# acceleration_particul_ariel.net
KiCad netlist of a schematic drawn in EasyEDA
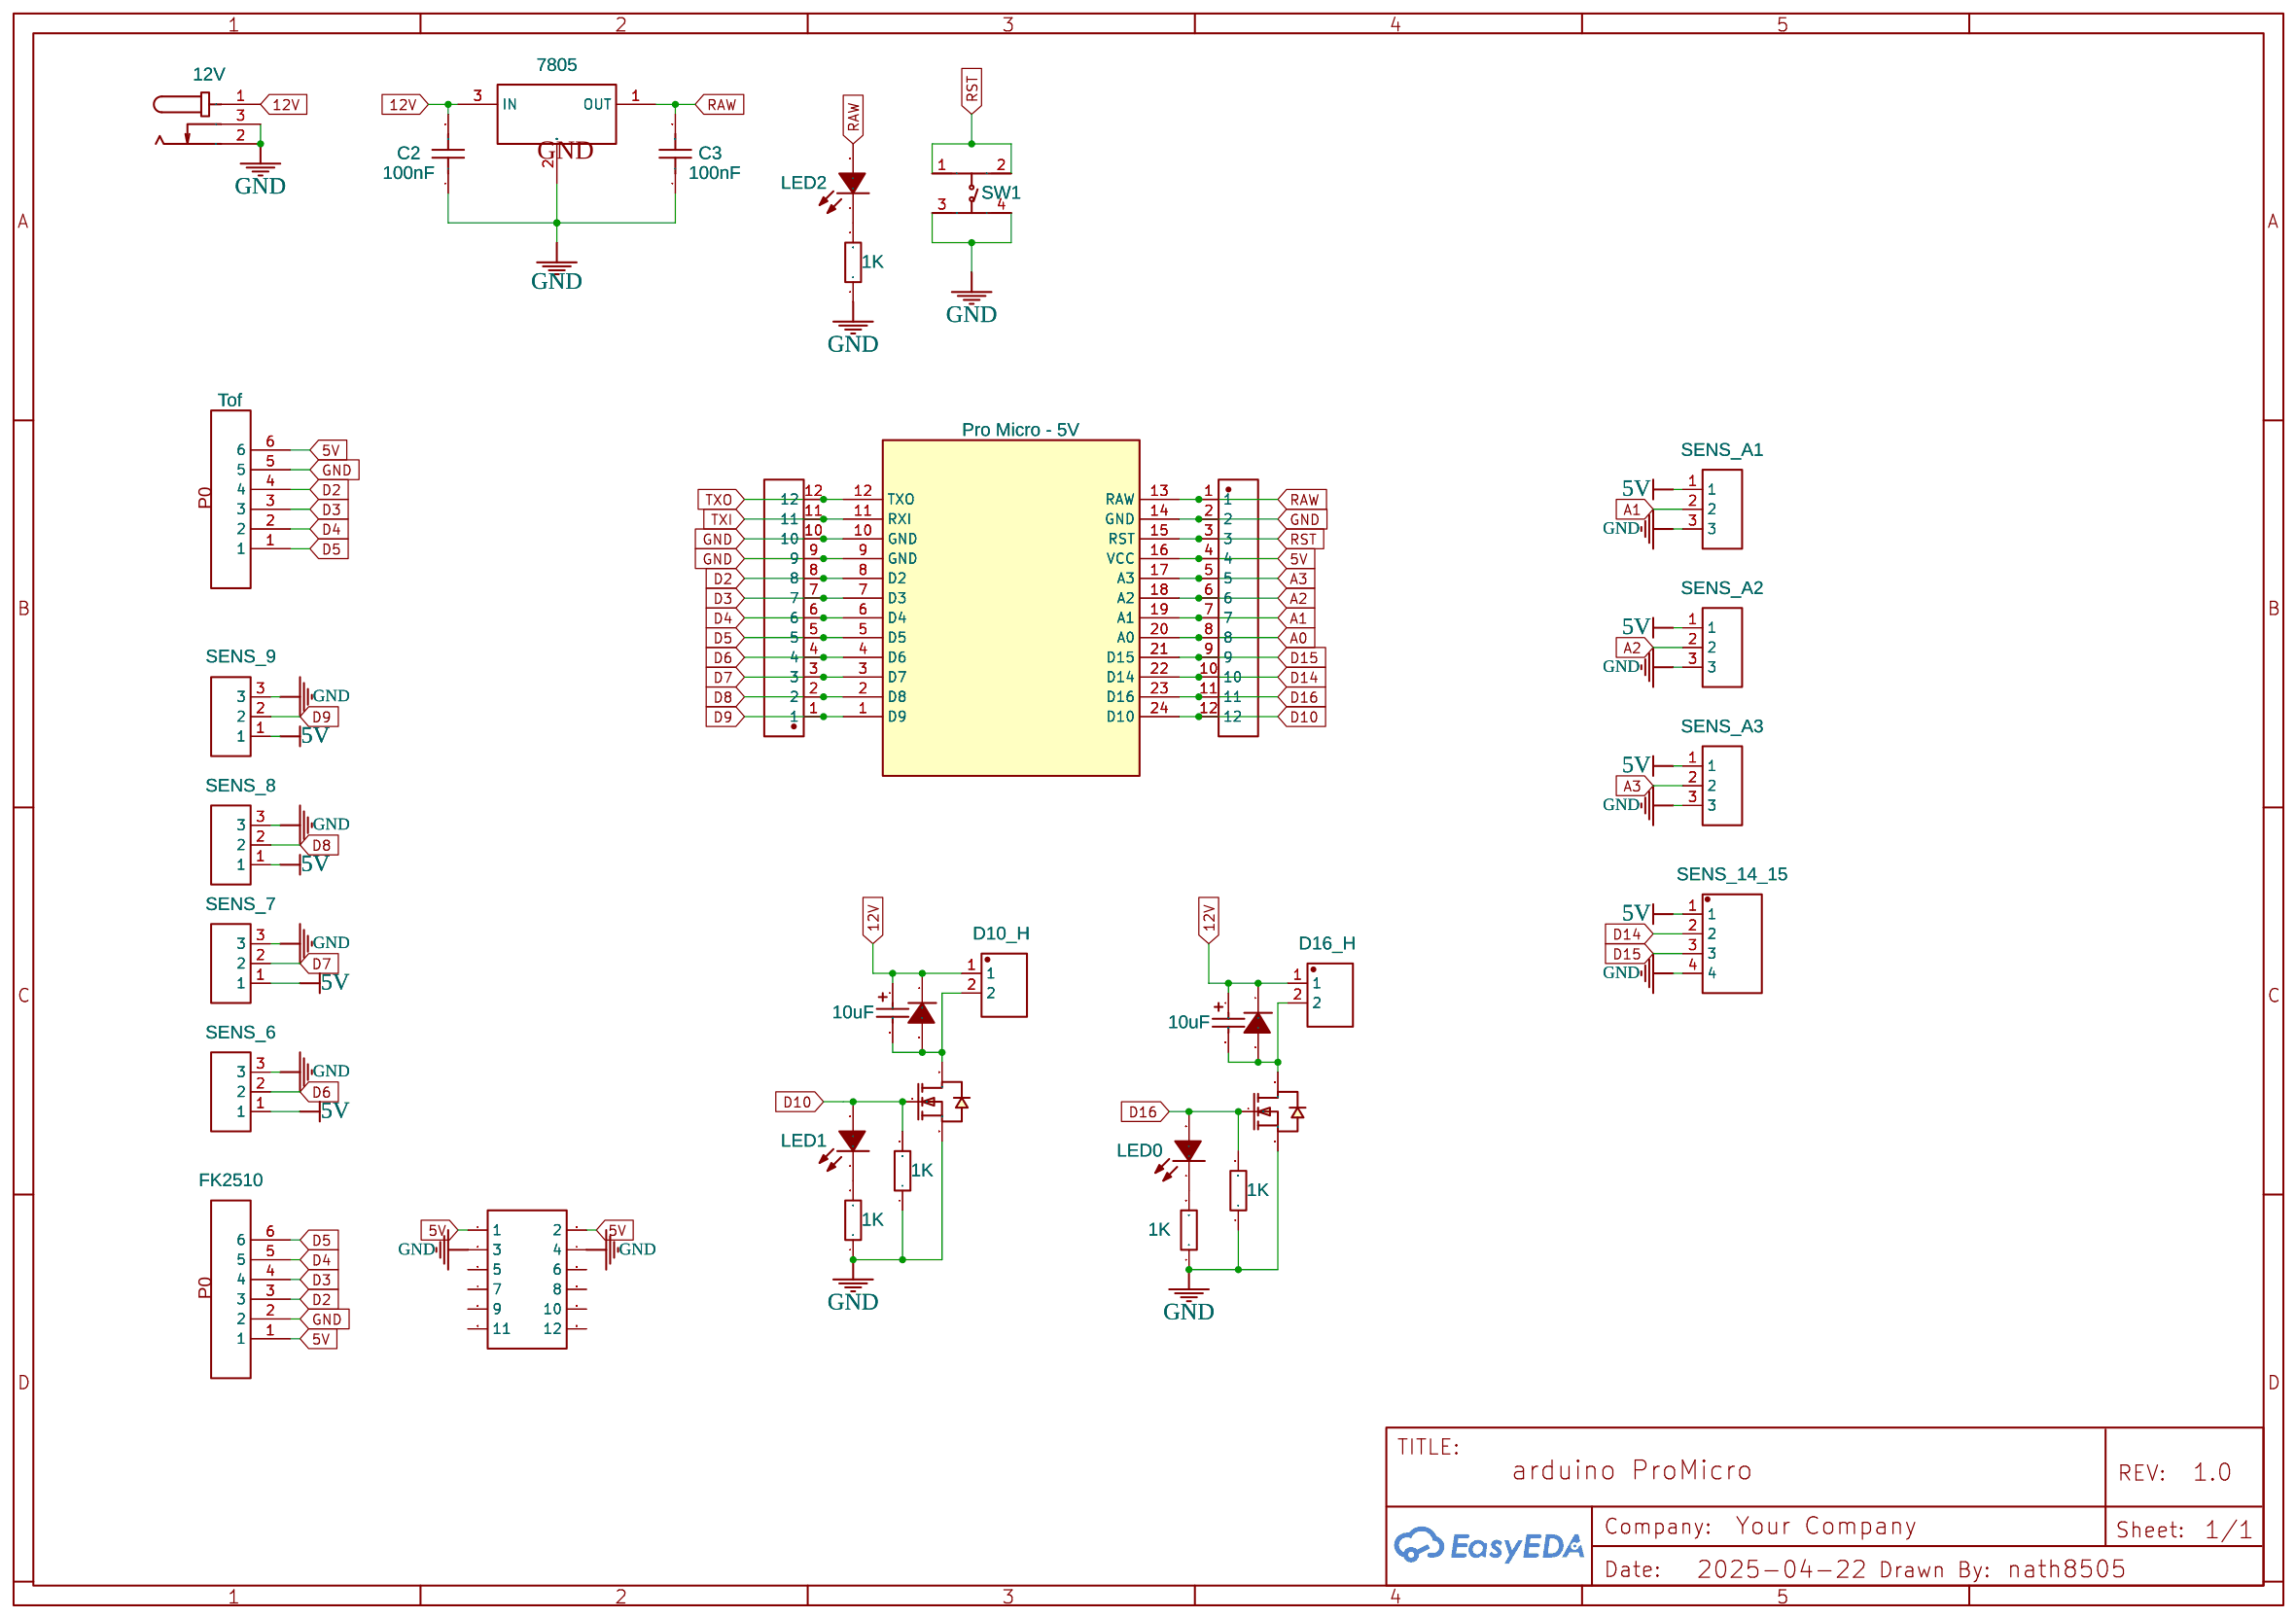
[diagram p0: schematic sheet]

(export (version "E")
  (design (tool "Eeschema 10.0.6"))
  (components
    (comp (ref "12V")
      (value "12V")
      (fields (field (name "Manufacturer Part") "DC005-2.0MM") (field (name "Manufacturer") "SOFNG"))
      (libsource (lib "") (part "DC005-2.0MM"))
    )
    (comp (ref "7805")
      (value "SE78L05")
      (fields (field (name "Manufacturer") "SEAWARD(思旺)"))
      (libsource (lib "") (part "SE78L05"))
    )
    (comp (ref "C0") (value "10uF") (libsource (lib "") (part "TAJA106K016RNJ")))
    (comp (ref "C1") (value "10uF") (libsource (lib "") (part "TAJA106K016RNJ")))
    (comp (ref "C2") (value "100nF") (libsource (lib "") (part "CC0603KRX7R9BB104")))
    (comp (ref "C3") (value "100nF") (libsource (lib "") (part "CC0603KRX7R9BB104")))
    (comp (ref "D0")
      (value "1N4007")
      (fields (field (name "Manufacturer Part") "1N4007F") (field (name "Manufacturer") "SK"))
      (libsource (lib "") (part "1N4007F"))
    )
    (comp (ref "D1")
      (value "1N4007")
      (fields (field (name "Manufacturer Part") "1N4007F") (field (name "Manufacturer") "SK"))
      (libsource (lib "") (part "1N4007F"))
    )
    (comp (ref "D10_H")
      (value "KF2510-2A")
      (fields (field (name "Manufacturer") "BOOMELE"))
      (libsource (lib "") (part "KF2510-2A_1"))
    )
    (comp (ref "D16_H")
      (value "KF2510-2A")
      (fields (field (name "Manufacturer") "BOOMELE"))
      (libsource (lib "") (part "KF2510-2A"))
    )
    (comp (ref "H1")
      (value "h")
      (fields (field (name "Manufacturer Part") "DS1021-1x12SF11-B") (field (name "Manufacturer") "CONNFLY"))
      (libsource (lib "") (part "DS1021-1X12SF11-B_1"))
    )
    (comp (ref "H2")
      (value "h")
      (fields (field (name "Manufacturer Part") "DS1021-1x12SF11-B") (field (name "Manufacturer") "CONNFLY"))
      (libsource (lib "") (part "DS1021-1X12SF11-B"))
    )
    (comp (ref "H4")
      (value "Header-Female-2.54_2x6")
      (fields (field (name "Manufacturer Part") "2.54-2*6P母") (field (name "Manufacturer") "BOOMELE(博穆精密)"))
      (libsource (lib "") (part "Header-Female-2.54_2x6"))
    )
    (comp (ref "I2C_TOF1") (value "Tof") (libsource (lib "") (part "PinHeader6")))
    (comp (ref "I2C_TOF2") (value "FK2510") (libsource (lib "") (part "PinHeader6")))
    (comp (ref "LED0")
      (value "KT-0603R")
      (fields (field (name "Manufacturer") "KENTO"))
      (libsource (lib "") (part "KT-0603R"))
    )
    (comp (ref "LED1")
      (value "KT-0603R")
      (fields (field (name "Manufacturer") "KENTO"))
      (libsource (lib "") (part "KT-0603R"))
    )
    (comp (ref "LED2")
      (value "KT-0603R")
      (fields (field (name "Manufacturer") "KENTO"))
      (libsource (lib "") (part "KT-0603R"))
    )
    (comp (ref "P2") (value "Pro Micro - 5V") (libsource (lib "") (part "Pro Micro - 5V")))
    (comp (ref "R0")
      (value "1K")
      (fields (field (name "Manufacturer Part") "0603WAF1001T5E") (field (name "Manufacturer") "UniOhm"))
      (libsource (lib "") (part "0603WAF1001T5E"))
    )
    (comp (ref "R1")
      (value "1K")
      (fields (field (name "Manufacturer Part") "0603WAF1001T5E") (field (name "Manufacturer") "UniOhm"))
      (libsource (lib "") (part "0603WAF1001T5E"))
    )
    (comp (ref "R2")
      (value "1K")
      (fields (field (name "Manufacturer Part") "0603WAF1001T5E") (field (name "Manufacturer") "UniOhm"))
      (libsource (lib "") (part "0603WAF1001T5E"))
    )
    (comp (ref "R3")
      (value "1K")
      (fields (field (name "Manufacturer Part") "0603WAF1001T5E") (field (name "Manufacturer") "UniOhm"))
      (libsource (lib "") (part "0603WAF1001T5E"))
    )
    (comp (ref "R4")
      (value "1K")
      (fields (field (name "Manufacturer Part") "0603WAF1001T5E") (field (name "Manufacturer") "UniOhm"))
      (libsource (lib "") (part "0603WAF1001T5E"))
    )
    (comp (ref "SENS_6") (value "FK2510") (libsource (lib "") (part "kf2510_3A")))
    (comp (ref "SENS_7") (value "FK2510") (libsource (lib "") (part "kf2510_3A")))
    (comp (ref "SENS_8") (value "FK2510") (libsource (lib "") (part "kf2510_3A")))
    (comp (ref "SENS_9") (value "FK2510") (libsource (lib "") (part "kf2510_3A")))
    (comp (ref "SENS_14_15")
      (value "SENS_14_15")
      (fields
        (field (name "Manufacturer Part") "210S-1*4P L=11.6MMGold-plated black")
        (field (name "Manufacturer") "Ckmtw")
      )
      (libsource (lib "") (part "Conector KF2510_3A.ventilador.4pin"))
    )
    (comp (ref "SENS_A1") (value "FK2510") (libsource (lib "") (part "kf2510_3A_1")))
    (comp (ref "SENS_A2") (value "FK2510") (libsource (lib "") (part "kf2510_3A_1")))
    (comp (ref "SENS_A3") (value "FK2510") (libsource (lib "") (part "kf2510_3A_1")))
    (comp (ref "SW1")
      (value "TC-6610-7-160G")
      (fields (field (name "Manufacturer") "HCTL(华灿天禄)"))
      (libsource (lib "") (part "TC-6610-7-160G"))
    )
    (comp (ref "T1")
      (value "Q")
      (fields (field (name "Manufacturer Part") "AO3400") (field (name "Manufacturer") "ElecSuper(静芯微）"))
      (libsource (lib "") (part "JSM2302"))
    )
    (comp (ref "T2")
      (value "Q")
      (fields (field (name "Manufacturer Part") "AO3400") (field (name "Manufacturer") "ElecSuper(静芯微）"))
      (libsource (lib "") (part "JSM2302"))
    )
  )
  (nets
    (net (code "1") (name "5V") (class "Default")
      (node (ref "H1") (pin "4") (pinfunction "4_4") (pintype "unspecified"))
      (node (ref "H4") (pin "1") (pinfunction "1_1") (pintype "input"))
      (node (ref "H4") (pin "2") (pinfunction "2_2") (pintype "input"))
      (node (ref "I2C_TOF1") (pin "6") (pinfunction "6_6") (pintype "unspecified"))
      (node (ref "I2C_TOF2") (pin "1") (pinfunction "1_1") (pintype "unspecified"))
      (node (ref "P2") (pin "16") (pinfunction "VCC_16") (pintype "unspecified"))
      (node (ref "SENS_14_15") (pin "1") (pinfunction "1_1") (pintype "unspecified"))
      (node (ref "SENS_6") (pin "1") (pinfunction "1_1") (pintype "unspecified"))
      (node (ref "SENS_7") (pin "1") (pinfunction "1_1") (pintype "unspecified"))
      (node (ref "SENS_8") (pin "1") (pinfunction "1_1") (pintype "unspecified"))
      (node (ref "SENS_9") (pin "1") (pinfunction "1_1") (pintype "unspecified"))
      (node (ref "SENS_A1") (pin "1") (pinfunction "1_1") (pintype "unspecified"))
      (node (ref "SENS_A2") (pin "1") (pinfunction "1_1") (pintype "unspecified"))
      (node (ref "SENS_A3") (pin "1") (pinfunction "1_1") (pintype "unspecified"))
    )
    (net (code "2") (name "12V") (class "Default")
      (node (ref "12V") (pin "1") (pinfunction "1_1") (pintype "unspecified"))
      (node (ref "7805") (pin "3") (pinfunction "IN_3") (pintype "passive"))
      (node (ref "C0") (pin "1") (pinfunction "1_1") (pintype "input"))
      (node (ref "C1") (pin "1") (pinfunction "1_1") (pintype "input"))
      (node (ref "C2") (pin "2") (pinfunction "2_2") (pintype "unspecified"))
      (node (ref "D0") (pin "1") (pinfunction "C_1") (pintype "unspecified"))
      (node (ref "D1") (pin "1") (pinfunction "C_1") (pintype "unspecified"))
      (node (ref "D10_H") (pin "1") (pinfunction "1_1") (pintype "unspecified"))
      (node (ref "D16_H") (pin "1") (pinfunction "1_1") (pintype "unspecified"))
    )
    (net (code "3") (name "A0") (class "Default")
      (node (ref "H1") (pin "8") (pinfunction "8_8") (pintype "unspecified"))
      (node (ref "P2") (pin "20") (pinfunction "A0_20") (pintype "unspecified"))
    )
    (net (code "4") (name "A1") (class "Default")
      (node (ref "H1") (pin "7") (pinfunction "7_7") (pintype "unspecified"))
      (node (ref "P2") (pin "19") (pinfunction "A1_19") (pintype "unspecified"))
      (node (ref "SENS_A1") (pin "2") (pinfunction "2_2") (pintype "unspecified"))
    )
    (net (code "5") (name "A2") (class "Default")
      (node (ref "H1") (pin "6") (pinfunction "6_6") (pintype "unspecified"))
      (node (ref "P2") (pin "18") (pinfunction "A2_18") (pintype "unspecified"))
      (node (ref "SENS_A2") (pin "2") (pinfunction "2_2") (pintype "unspecified"))
    )
    (net (code "6") (name "A3") (class "Default")
      (node (ref "H1") (pin "5") (pinfunction "5_5") (pintype "unspecified"))
      (node (ref "P2") (pin "17") (pinfunction "A3_17") (pintype "unspecified"))
      (node (ref "SENS_A3") (pin "2") (pinfunction "2_2") (pintype "unspecified"))
    )
    (net (code "7") (name "D2") (class "Default")
      (node (ref "H2") (pin "8") (pinfunction "8_8") (pintype "unspecified"))
      (node (ref "I2C_TOF1") (pin "4") (pinfunction "4_4") (pintype "unspecified"))
      (node (ref "I2C_TOF2") (pin "3") (pinfunction "3_3") (pintype "unspecified"))
      (node (ref "P2") (pin "8") (pinfunction "D2_8") (pintype "unspecified"))
    )
    (net (code "8") (name "D3") (class "Default")
      (node (ref "H2") (pin "7") (pinfunction "7_7") (pintype "unspecified"))
      (node (ref "I2C_TOF1") (pin "3") (pinfunction "3_3") (pintype "unspecified"))
      (node (ref "I2C_TOF2") (pin "4") (pinfunction "4_4") (pintype "unspecified"))
      (node (ref "P2") (pin "7") (pinfunction "D3_7") (pintype "unspecified"))
    )
    (net (code "9") (name "D4") (class "Default")
      (node (ref "H2") (pin "6") (pinfunction "6_6") (pintype "unspecified"))
      (node (ref "I2C_TOF1") (pin "2") (pinfunction "2_2") (pintype "unspecified"))
      (node (ref "I2C_TOF2") (pin "5") (pinfunction "5_5") (pintype "unspecified"))
      (node (ref "P2") (pin "6") (pinfunction "D4_6") (pintype "unspecified"))
    )
    (net (code "10") (name "D5") (class "Default")
      (node (ref "H2") (pin "5") (pinfunction "5_5") (pintype "unspecified"))
      (node (ref "I2C_TOF1") (pin "1") (pinfunction "1_1") (pintype "unspecified"))
      (node (ref "I2C_TOF2") (pin "6") (pinfunction "6_6") (pintype "unspecified"))
      (node (ref "P2") (pin "5") (pinfunction "D5_5") (pintype "unspecified"))
    )
    (net (code "11") (name "D6") (class "Default")
      (node (ref "H2") (pin "4") (pinfunction "4_4") (pintype "unspecified"))
      (node (ref "P2") (pin "4") (pinfunction "D6_4") (pintype "unspecified"))
      (node (ref "SENS_6") (pin "2") (pinfunction "2_2") (pintype "unspecified"))
    )
    (net (code "12") (name "D7") (class "Default")
      (node (ref "H2") (pin "3") (pinfunction "3_3") (pintype "unspecified"))
      (node (ref "P2") (pin "3") (pinfunction "D7_3") (pintype "unspecified"))
      (node (ref "SENS_7") (pin "2") (pinfunction "2_2") (pintype "unspecified"))
    )
    (net (code "13") (name "D8") (class "Default")
      (node (ref "H2") (pin "2") (pinfunction "2_2") (pintype "unspecified"))
      (node (ref "P2") (pin "2") (pinfunction "D8_2") (pintype "unspecified"))
      (node (ref "SENS_8") (pin "2") (pinfunction "2_2") (pintype "unspecified"))
    )
    (net (code "14") (name "D9") (class "Default")
      (node (ref "H2") (pin "1") (pinfunction "1_1") (pintype "unspecified"))
      (node (ref "P2") (pin "1") (pinfunction "D9_1") (pintype "unspecified"))
      (node (ref "SENS_9") (pin "2") (pinfunction "2_2") (pintype "unspecified"))
    )
    (net (code "15") (name "D10") (class "Default")
      (node (ref "H1") (pin "12") (pinfunction "12_12") (pintype "unspecified"))
      (node (ref "LED1") (pin "2") (pinfunction "A_2") (pintype "unspecified"))
      (node (ref "P2") (pin "24") (pinfunction "D10_24") (pintype "unspecified"))
      (node (ref "R2") (pin "2") (pinfunction "2_2") (pintype "input"))
      (node (ref "T1") (pin "1") (pinfunction "G_1") (pintype "unspecified"))
    )
    (net (code "16") (name "D14") (class "Default")
      (node (ref "H1") (pin "10") (pinfunction "10_10") (pintype "unspecified"))
      (node (ref "P2") (pin "22") (pinfunction "D14_22") (pintype "unspecified"))
      (node (ref "SENS_14_15") (pin "2") (pinfunction "2_2") (pintype "unspecified"))
    )
    (net (code "17") (name "D15") (class "Default")
      (node (ref "H1") (pin "9") (pinfunction "9_9") (pintype "unspecified"))
      (node (ref "P2") (pin "21") (pinfunction "D15_21") (pintype "unspecified"))
      (node (ref "SENS_14_15") (pin "3") (pinfunction "3_3") (pintype "unspecified"))
    )
    (net (code "18") (name "D16") (class "Default")
      (node (ref "H1") (pin "11") (pinfunction "11_11") (pintype "unspecified"))
      (node (ref "LED0") (pin "2") (pinfunction "A_2") (pintype "unspecified"))
      (node (ref "P2") (pin "23") (pinfunction "D16_23") (pintype "unspecified"))
      (node (ref "R1") (pin "2") (pinfunction "2_2") (pintype "input"))
      (node (ref "T2") (pin "1") (pinfunction "G_1") (pintype "unspecified"))
    )
    (net (code "19") (name "GND") (class "Default")
      (node (ref "12V") (pin "2") (pinfunction "2_2") (pintype "unspecified"))
      (node (ref "12V") (pin "3") (pinfunction "3_3") (pintype "unspecified"))
      (node (ref "7805") (pin "2") (pinfunction "GND_2") (pintype "unspecified"))
      (node (ref "C2") (pin "1") (pinfunction "1_1") (pintype "unspecified"))
      (node (ref "C3") (pin "1") (pinfunction "1_1") (pintype "unspecified"))
      (node (ref "H1") (pin "2") (pinfunction "2_2") (pintype "unspecified"))
      (node (ref "H2") (pin "10") (pinfunction "10_10") (pintype "unspecified"))
      (node (ref "H2") (pin "9") (pinfunction "9_9") (pintype "unspecified"))
      (node (ref "H4") (pin "3") (pinfunction "3_3") (pintype "input"))
      (node (ref "H4") (pin "4") (pinfunction "4_4") (pintype "input"))
      (node (ref "I2C_TOF1") (pin "5") (pinfunction "5_5") (pintype "unspecified"))
      (node (ref "I2C_TOF2") (pin "2") (pinfunction "2_2") (pintype "unspecified"))
      (node (ref "P2") (pin "10") (pinfunction "GND_10") (pintype "unspecified"))
      (node (ref "P2") (pin "14") (pinfunction "GND_14") (pintype "unspecified"))
      (node (ref "P2") (pin "9") (pinfunction "GND_9") (pintype "unspecified"))
      (node (ref "R0") (pin "1") (pinfunction "1_1") (pintype "input"))
      (node (ref "R1") (pin "1") (pinfunction "1_1") (pintype "input"))
      (node (ref "R2") (pin "1") (pinfunction "1_1") (pintype "input"))
      (node (ref "R3") (pin "1") (pinfunction "1_1") (pintype "input"))
      (node (ref "R4") (pin "1") (pinfunction "1_1") (pintype "input"))
      (node (ref "SENS_14_15") (pin "4") (pinfunction "4_4") (pintype "unspecified"))
      (node (ref "SENS_6") (pin "3") (pinfunction "3_3") (pintype "unspecified"))
      (node (ref "SENS_7") (pin "3") (pinfunction "3_3") (pintype "unspecified"))
      (node (ref "SENS_8") (pin "3") (pinfunction "3_3") (pintype "unspecified"))
      (node (ref "SENS_9") (pin "3") (pinfunction "3_3") (pintype "unspecified"))
      (node (ref "SENS_A1") (pin "3") (pinfunction "3_3") (pintype "unspecified"))
      (node (ref "SENS_A2") (pin "3") (pinfunction "3_3") (pintype "unspecified"))
      (node (ref "SENS_A3") (pin "3") (pinfunction "3_3") (pintype "unspecified"))
      (node (ref "SW1") (pin "3") (pinfunction "3_3") (pintype "unspecified"))
      (node (ref "SW1") (pin "4") (pinfunction "4_4") (pintype "unspecified"))
      (node (ref "T1") (pin "2") (pinfunction "S_2") (pintype "unspecified"))
      (node (ref "T2") (pin "2") (pinfunction "S_2") (pintype "unspecified"))
    )
    (net (code "20") (name "Net-(D0-A)") (class "Default")
      (node (ref "C0") (pin "2") (pinfunction "2_2") (pintype "input"))
      (node (ref "D0") (pin "2") (pinfunction "A_2") (pintype "unspecified"))
      (node (ref "D10_H") (pin "2") (pinfunction "2_2") (pintype "unspecified"))
      (node (ref "T1") (pin "3") (pinfunction "D_3") (pintype "unspecified"))
    )
    (net (code "21") (name "Net-(D1-A)") (class "Default")
      (node (ref "C1") (pin "2") (pinfunction "2_2") (pintype "input"))
      (node (ref "D1") (pin "2") (pinfunction "A_2") (pintype "unspecified"))
      (node (ref "D16_H") (pin "2") (pinfunction "2_2") (pintype "unspecified"))
      (node (ref "T2") (pin "3") (pinfunction "D_3") (pintype "unspecified"))
    )
    (net (code "22") (name "Net-(LED0-K)") (class "Default")
      (node (ref "LED0") (pin "1") (pinfunction "K_1") (pintype "unspecified"))
      (node (ref "R0") (pin "2") (pinfunction "2_2") (pintype "input"))
    )
    (net (code "23") (name "Net-(LED1-K)") (class "Default")
      (node (ref "LED1") (pin "1") (pinfunction "K_1") (pintype "unspecified"))
      (node (ref "R3") (pin "2") (pinfunction "2_2") (pintype "input"))
    )
    (net (code "24") (name "Net-(LED2-K)") (class "Default")
      (node (ref "LED2") (pin "1") (pinfunction "K_1") (pintype "unspecified"))
      (node (ref "R4") (pin "2") (pinfunction "2_2") (pintype "input"))
    )
    (net (code "25") (name "RAW") (class "Default")
      (node (ref "7805") (pin "1") (pinfunction "OUT_1") (pintype "passive"))
      (node (ref "C3") (pin "2") (pinfunction "2_2") (pintype "unspecified"))
      (node (ref "H1") (pin "1") (pinfunction "1_1") (pintype "unspecified"))
      (node (ref "LED2") (pin "2") (pinfunction "A_2") (pintype "unspecified"))
      (node (ref "P2") (pin "13") (pinfunction "RAW_13") (pintype "unspecified"))
    )
    (net (code "26") (name "RST") (class "Default")
      (node (ref "H1") (pin "3") (pinfunction "3_3") (pintype "unspecified"))
      (node (ref "P2") (pin "15") (pinfunction "RST_15") (pintype "unspecified"))
      (node (ref "SW1") (pin "1") (pinfunction "1_1") (pintype "unspecified"))
      (node (ref "SW1") (pin "2") (pinfunction "2_2") (pintype "unspecified"))
    )
    (net (code "27") (name "TXI") (class "Default")
      (node (ref "H2") (pin "11") (pinfunction "11_11") (pintype "unspecified"))
      (node (ref "P2") (pin "11") (pinfunction "RXI_11") (pintype "unspecified"))
    )
    (net (code "28") (name "TXO") (class "Default")
      (node (ref "H2") (pin "12") (pinfunction "12_12") (pintype "unspecified"))
      (node (ref "P2") (pin "12") (pinfunction "TXO_12") (pintype "unspecified"))
    )
    (net (code "29") (name "unconnected-(H4-Pad5)") (class "Default")
      (node (ref "H4") (pin "5") (pinfunction "5_5") (pintype "input"))
    )
    (net (code "30") (name "unconnected-(H4-Pad6)") (class "Default")
      (node (ref "H4") (pin "6") (pinfunction "6_6") (pintype "input"))
    )
    (net (code "31") (name "unconnected-(H4-Pad7)") (class "Default")
      (node (ref "H4") (pin "7") (pinfunction "7_7") (pintype "input"))
    )
    (net (code "32") (name "unconnected-(H4-Pad8)") (class "Default")
      (node (ref "H4") (pin "8") (pinfunction "8_8") (pintype "input"))
    )
    (net (code "33") (name "unconnected-(H4-Pad9)") (class "Default")
      (node (ref "H4") (pin "9") (pinfunction "9_9") (pintype "input"))
    )
    (net (code "34") (name "unconnected-(H4-Pad10)") (class "Default")
      (node (ref "H4") (pin "10") (pinfunction "10_10") (pintype "input"))
    )
    (net (code "35") (name "unconnected-(H4-Pad11)") (class "Default")
      (node (ref "H4") (pin "11") (pinfunction "11_11") (pintype "input"))
    )
    (net (code "36") (name "unconnected-(H4-Pad12)") (class "Default")
      (node (ref "H4") (pin "12") (pinfunction "12_12") (pintype "input"))
    )
  )
)
